# Doorlock-ESP32-copy_2026-03-03.net
KiCad netlist of a schematic drawn in Altium Designer
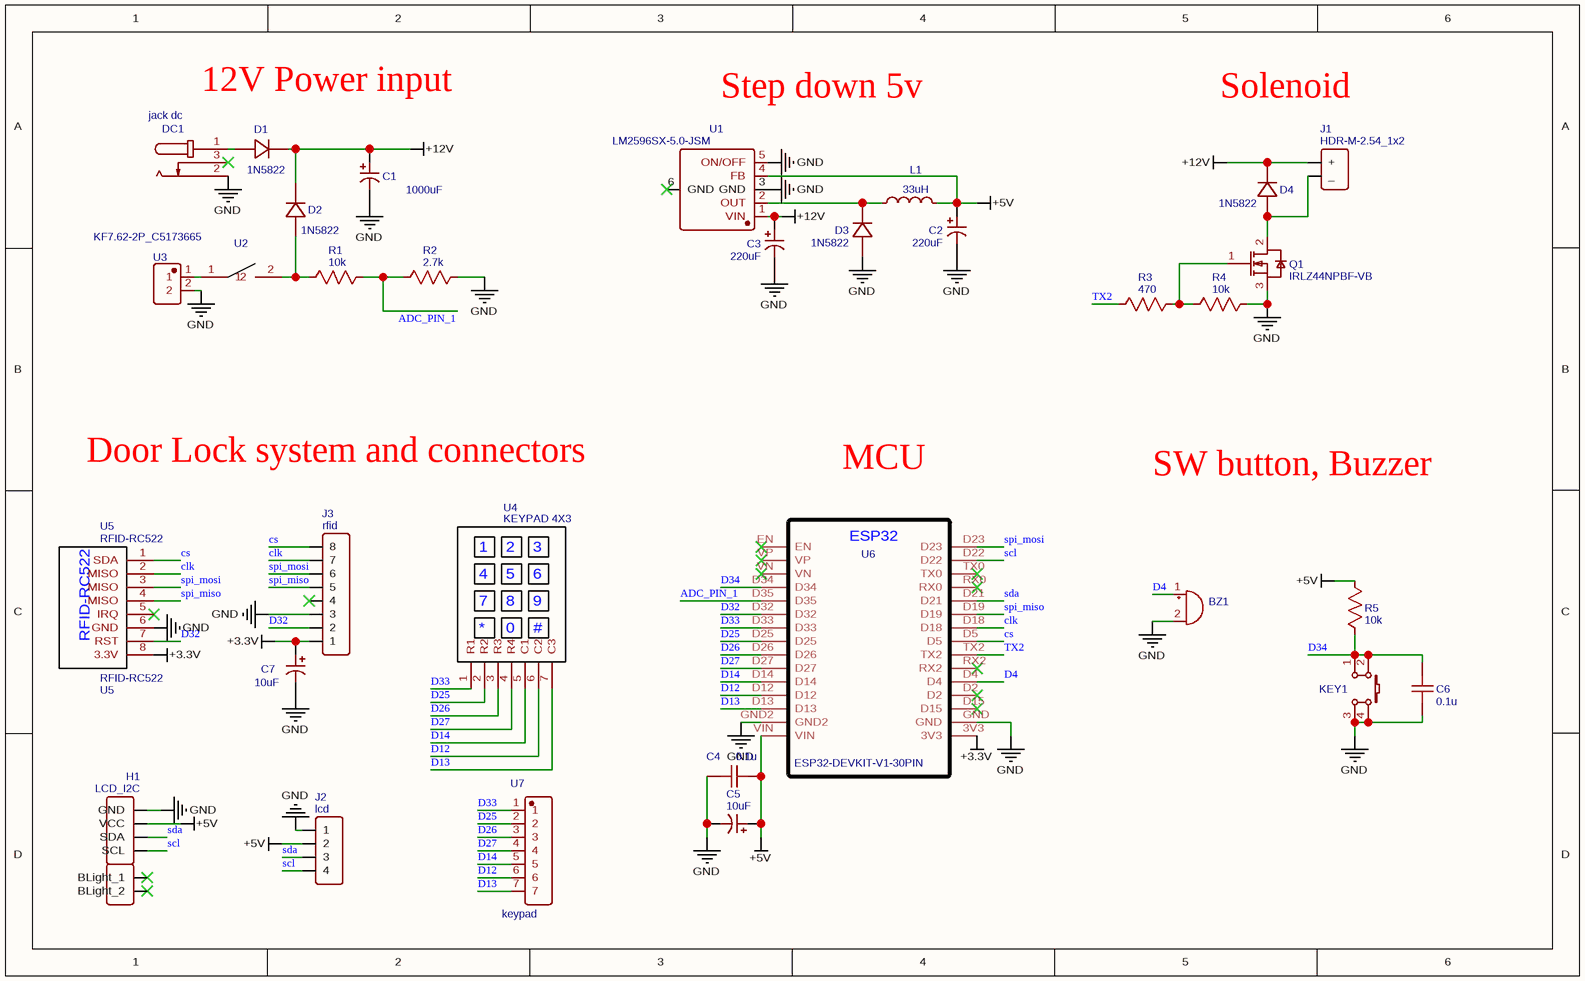
[diagram p0: Doorlock-ESP32-copy_2026-03-03.schdoc]

(export (version "E")
  (design (tool "Eeschema 10.0.6"))
  (components
    (comp (ref "BZ1")
      (value "DEVICE_BUZZER")
      (fields (field (name "CONTRIBUTOR") "anhnguyen0904255"))
      (libsource (lib "altium-import") (part "root_0_DEVICE_BUZZER_"))
    )
    (comp (ref "C1")
      (value "1000uF")
      (fields
        (field (name "MANUFACTURER") "HRK(鸿瑞凯电子)")
        (field (name "MANUFACTURER PART") "25V1000uF CD110")
        (field (name "CONTRIBUTOR") "lcsc")
      )
      (libsource (lib "altium-import") (part "root_3_1000uF_"))
    )
    (comp (ref "C2")
      (value "220uF")
      (fields
        (field (name "MANUFACTURER") "HRK(鸿瑞凯电子)")
        (field (name "MANUFACTURER PART") "25V1000uF CD110")
        (field (name "CONTRIBUTOR") "lcsc")
      )
      (libsource (lib "altium-import") (part "root_3_220uF_"))
    )
    (comp (ref "C3")
      (value "220uF")
      (fields
        (field (name "MANUFACTURER") "HRK(鸿瑞凯电子)")
        (field (name "MANUFACTURER PART") "25V1000uF CD110")
        (field (name "CONTRIBUTOR") "lcsc")
      )
      (libsource (lib "altium-import") (part "root_3_220uF_"))
    )
    (comp (ref "C4")
      (value "0.1u")
      (fields (field (name "CONTRIBUTOR") "LCEDA_Lib"))
      (libsource (lib "altium-import") (part "root_2_0.1u_"))
    )
    (comp (ref "C5")
      (value "10uF")
      (fields
        (field (name "MANUFACTURER") "Econd(米朗电子)")
        (field (name "MANUFACTURER PART") "10UF50VC110GL")
        (field (name "CONTRIBUTOR") "lcsc")
      )
      (libsource (lib "altium-import") (part "root_2_10uF_"))
    )
    (comp (ref "C6")
      (value "0.1u")
      (fields (field (name "CONTRIBUTOR") "LCEDA_Lib"))
      (libsource (lib "altium-import") (part "root_1_0.1u_"))
    )
    (comp (ref "C7")
      (value "10uF")
      (fields
        (field (name "MANUFACTURER") "Econd(米朗电子)")
        (field (name "MANUFACTURER PART") "10UF50VC110GL")
        (field (name "CONTRIBUTOR") "lcsc")
      )
      (libsource (lib "altium-import") (part "root_3_10uF_"))
    )
    (comp (ref "D1")
      (value "1N5822")
      (fields
        (field (name "MANUFACTURER") "YFW(佑风微)")
        (field (name "MANUFACTURER PART") "1N5819散装0658")
        (field (name "CONTRIBUTOR") "lcsc")
      )
      (libsource (lib "altium-import") (part "root_2_1N5822_"))
    )
    (comp (ref "D2")
      (value "1N5822")
      (fields
        (field (name "MANUFACTURER") "YFW(佑风微)")
        (field (name "MANUFACTURER PART") "1N5819散装0658")
        (field (name "CONTRIBUTOR") "lcsc")
      )
      (libsource (lib "altium-import") (part "root_3_1N5822_"))
    )
    (comp (ref "D3")
      (value "1N5822")
      (fields
        (field (name "MANUFACTURER") "YFW(佑风微)")
        (field (name "MANUFACTURER PART") "1N5819散装0658")
        (field (name "CONTRIBUTOR") "lcsc")
      )
      (libsource (lib "") (part "root_3_1N5822__1"))
    )
    (comp (ref "D4")
      (value "1N5822")
      (fields
        (field (name "MANUFACTURER") "YFW(佑风微)")
        (field (name "MANUFACTURER PART") "1N5819散装0658")
        (field (name "CONTRIBUTOR") "lcsc")
      )
      (libsource (lib "altium-import") (part "root_3_1N5822_"))
    )
    (comp (ref "DC1")
      (value "jack dc")
      (fields (field (name "MANUFACTURER") "SOFNG") (field (name "MANUFACTURER PART") "DC005-2.0MM"))
      (libsource (lib "altium-import") (part "root_0_jack dc_"))
    )
    (comp (ref "H1")
      (value "LCD_I2C")
      (fields (field (name "SUBPART_NO") "1") (field (name "CONTRIBUTOR") "amadosumbi3"))
      (libsource (lib "altium-import") (part "root_0_LCD_I2C_"))
    )
    (comp (ref "J1")
      (value "HDR-M-2.54_1x2")
      (fields (field (name "CONTRIBUTOR") "LCEDA_Lib"))
      (libsource (lib "altium-import") (part "root_0_HDR-M-2.54_1x2_"))
    )
    (comp (ref "J2")
      (value "lcd")
      (fields (field (name "CONTRIBUTOR") "LCEDA_Lib"))
      (libsource (lib "altium-import") (part "root_0_lcd_"))
    )
    (comp (ref "J3")
      (value "rfid")
      (fields (field (name "CONTRIBUTOR") "LCEDA_Lib"))
      (libsource (lib "altium-import") (part "root_2_rfid_"))
    )
    (comp (ref "KEY1")
      (value "K4-12×12_TH")
      (fields
        (field (name "MANUFACTURER") "韩国韩荣")
        (field (name "MANUFACTURER PART") "K2-1103DP-M4SW-04")
        (field (name "CONTRIBUTOR") "LCEDA_Lib")
      )
      (libsource (lib "altium-import") (part "root_3_K4-12×12_TH_"))
    )
    (comp (ref "L1")
      (value "33uH")
      (fields (field (name "CONTRIBUTOR") "LCEDA_Lib"))
      (libsource (lib "altium-import") (part "root_0_33uH_"))
    )
    (comp (ref "Q1")
      (value "IRLZ44NPBF-VB")
      (fields (field (name "MANUFACTURER") "VBsemi(微碧半导体)") (field (name "CONTRIBUTOR") "lcsc"))
      (libsource (lib "altium-import") (part "root_0_IRLZ44NPBF-VB_"))
    )
    (comp (ref "R1")
      (value "10k")
      (fields (field (name "CONTRIBUTOR") "LCEDA_Lib"))
      (libsource (lib "altium-import") (part "root_0_10k_"))
    )
    (comp (ref "R2")
      (value "2.7k")
      (fields (field (name "CONTRIBUTOR") "LCEDA_Lib"))
      (libsource (lib "altium-import") (part "root_0_2.7k_"))
    )
    (comp (ref "R3")
      (value "470")
      (fields (field (name "CONTRIBUTOR") "LCEDA_Lib"))
      (libsource (lib "altium-import") (part "root_0_470_"))
    )
    (comp (ref "R4")
      (value "10k")
      (fields (field (name "CONTRIBUTOR") "LCEDA_Lib"))
      (libsource (lib "altium-import") (part "root_0_10k_"))
    )
    (comp (ref "R5")
      (value "10k")
      (fields (field (name "CONTRIBUTOR") "LCEDA_Lib"))
      (libsource (lib "altium-import") (part "root_3_10k_"))
    )
    (comp (ref "U1")
      (value "LM2596SX-5.0-JSM")
      (fields (field (name "MANUFACTURER") "JSMSEMI(杰盛微)") (field (name "CONTRIBUTOR") "lcsc"))
      (libsource (lib "altium-import") (part "root_2_LM2596SX-5.0-JSM_"))
    )
    (comp (ref "U2")
      (value "HX KCD1-2P-P")
      (fields (field (name "MANUFACTURER") "hanxia(韩下)") (field (name "CONTRIBUTOR") "lcsc"))
      (libsource (lib "altium-import") (part "root_0_HX KCD1-2P-P_"))
    )
    (comp (ref "U3")
      (value "KF7.62-2P_C5173665")
      (fields
        (field (name "MANUFACTURER") "KEFA(科发)")
        (field (name "MANUFACTURER PART") "KF7.62-2P(green)")
        (field (name "CONTRIBUTOR") "lcsc")
      )
      (libsource (lib "altium-import") (part "root_0_KF7.62-2P_C5173665_"))
    )
    (comp (ref "U4")
      (value "KEYPAD 4X3")
      (fields (field (name "CONTRIBUTOR") "lucas.vissers"))
      (libsource (lib "altium-import") (part "root_0_KEYPAD 4X3_"))
    )
    (comp (ref "U5")
      (value "RFID-RC522")
      (fields (field (name "CONTRIBUTOR") "mayurharge"))
      (libsource (lib "altium-import") (part "root_0_RFID-RC522_"))
    )
    (comp (ref "U6")
      (value "ESP32-DEVKIT-V1-30PIN")
      (fields (field (name "CONTRIBUTOR") "juergs"))
      (libsource (lib "altium-import") (part "root_0_ESP32-DEVKIT-V1-30PIN_"))
    )
    (comp (ref "U7")
      (value "keypad")
      (fields (field (name "MANUFACTURER PART") "PZ2.54-1X7P-ZW") (field (name "CONTRIBUTOR") "LCSC"))
      (libsource (lib "altium-import") (part "root_2_keypad_"))
    )
  )
  (nets
    (net (code "1") (name "+3.3V") (class "Default")
      (node (ref "C7") (pin "1") (pinfunction "1_1") (pintype "passive"))
      (node (ref "J3") (pin "1") (pinfunction "1_1") (pintype "passive"))
      (node (ref "U5") (pin "8") (pinfunction "3.3V_8") (pintype "passive"))
      (node (ref "U6") (pin "3V3") (pinfunction "3V3_3V3") (pintype "passive"))
    )
    (net (code "2") (name "+5V") (class "Default")
      (node (ref "C2") (pin "1") (pinfunction "1_1") (pintype "passive"))
      (node (ref "C4") (pin "1") (pinfunction "1_1") (pintype "passive"))
      (node (ref "C5") (pin "1") (pinfunction "1_1") (pintype "passive"))
      (node (ref "H1") (pin "2") (pinfunction "VCC_2") (pintype "passive"))
      (node (ref "J2") (pin "2") (pinfunction "2_2") (pintype "passive"))
      (node (ref "L1") (pin "2") (pinfunction "2_2") (pintype "passive"))
      (node (ref "R5") (pin "1") (pinfunction "1_1") (pintype "passive"))
      (node (ref "U1") (pin "4") (pinfunction "FB_4") (pintype "passive"))
      (node (ref "U6") (pin "VIN") (pinfunction "VIN_VIN") (pintype "passive"))
    )
    (net (code "3") (name "+12V") (class "Default")
      (node (ref "C1") (pin "1") (pinfunction "1_1") (pintype "passive"))
      (node (ref "C3") (pin "1") (pinfunction "1_1") (pintype "passive"))
      (node (ref "D1") (pin "1") (pinfunction "K_1") (pintype "passive"))
      (node (ref "D2") (pin "1") (pinfunction "K_1") (pintype "passive"))
      (node (ref "D4") (pin "1") (pinfunction "K_1") (pintype "passive"))
      (node (ref "J1") (pin "1") (pinfunction "+_1") (pintype "passive"))
      (node (ref "U1") (pin "1") (pinfunction "VIN_1") (pintype "passive"))
    )
    (net (code "4") (name "/ADC_PIN_1") (class "Default")
      (node (ref "R1") (pin "2") (pinfunction "2_2") (pintype "passive"))
      (node (ref "R2") (pin "1") (pinfunction "1_1") (pintype "passive"))
      (node (ref "U6") (pin "D35") (pinfunction "D35_D35") (pintype "passive"))
    )
    (net (code "5") (name "/D4") (class "Default")
      (node (ref "BZ1") (pin "1") (pinfunction "+_1") (pintype "passive"))
      (node (ref "U6") (pin "D4") (pinfunction "D4_D4") (pintype "passive"))
    )
    (net (code "6") (name "/D12") (class "Default")
      (node (ref "U4") (pin "6") (pinfunction "C2_6") (pintype "passive"))
      (node (ref "U6") (pin "D12") (pinfunction "D12_D12") (pintype "passive"))
      (node (ref "U7") (pin "6") (pinfunction "6_6") (pintype "passive"))
    )
    (net (code "7") (name "/D13") (class "Default")
      (node (ref "U4") (pin "7") (pinfunction "C3_7") (pintype "passive"))
      (node (ref "U6") (pin "D13") (pinfunction "D13_D13") (pintype "passive"))
      (node (ref "U7") (pin "7") (pinfunction "7_7") (pintype "passive"))
    )
    (net (code "8") (name "/D14") (class "Default")
      (node (ref "U4") (pin "5") (pinfunction "C1_5") (pintype "passive"))
      (node (ref "U6") (pin "D14") (pinfunction "D14_D14") (pintype "passive"))
      (node (ref "U7") (pin "5") (pinfunction "5_5") (pintype "passive"))
    )
    (net (code "9") (name "/D25") (class "Default")
      (node (ref "U4") (pin "2") (pinfunction "R2_2") (pintype "passive"))
      (node (ref "U6") (pin "D25") (pinfunction "D25_D25") (pintype "passive"))
      (node (ref "U7") (pin "2") (pinfunction "2_2") (pintype "passive"))
    )
    (net (code "10") (name "/D26") (class "Default")
      (node (ref "U4") (pin "3") (pinfunction "R3_3") (pintype "passive"))
      (node (ref "U6") (pin "D26") (pinfunction "D26_D26") (pintype "passive"))
      (node (ref "U7") (pin "3") (pinfunction "3_3") (pintype "passive"))
    )
    (net (code "11") (name "/D27") (class "Default")
      (node (ref "U4") (pin "4") (pinfunction "R4_4") (pintype "passive"))
      (node (ref "U6") (pin "D27") (pinfunction "D27_D27") (pintype "passive"))
      (node (ref "U7") (pin "4") (pinfunction "4_4") (pintype "passive"))
    )
    (net (code "12") (name "/D32") (class "Default")
      (node (ref "J3") (pin "2") (pinfunction "2_2") (pintype "passive"))
      (node (ref "U5") (pin "7") (pinfunction "RST_7") (pintype "passive"))
      (node (ref "U6") (pin "D32") (pinfunction "D32_D32") (pintype "passive"))
    )
    (net (code "13") (name "/D33") (class "Default")
      (node (ref "U4") (pin "1") (pinfunction "R1_1") (pintype "passive"))
      (node (ref "U6") (pin "D33") (pinfunction "D33_D33") (pintype "passive"))
      (node (ref "U7") (pin "1") (pinfunction "1_1") (pintype "passive"))
    )
    (net (code "14") (name "/D34") (class "Default")
      (node (ref "C6") (pin "2") (pinfunction "2_2") (pintype "passive"))
      (node (ref "KEY1") (pin "1") (pinfunction "1_1") (pintype "passive"))
      (node (ref "KEY1") (pin "2") (pinfunction "2_2") (pintype "passive"))
      (node (ref "R5") (pin "2") (pinfunction "2_2") (pintype "passive"))
      (node (ref "U6") (pin "D34") (pinfunction "D34_D34") (pintype "passive"))
    )
    (net (code "15") (name "/TX2") (class "Default")
      (node (ref "R3") (pin "1") (pinfunction "1_1") (pintype "passive"))
      (node (ref "U6") (pin "TX2") (pinfunction "TX2_TX2") (pintype "passive"))
    )
    (net (code "16") (name "/clk") (class "Default")
      (node (ref "J3") (pin "7") (pinfunction "7_7") (pintype "passive"))
      (node (ref "U5") (pin "2") (pinfunction "MISO_2") (pintype "passive"))
      (node (ref "U6") (pin "D18") (pinfunction "D18_D18") (pintype "passive"))
    )
    (net (code "17") (name "/cs") (class "Default")
      (node (ref "J3") (pin "8") (pinfunction "8_8") (pintype "passive"))
      (node (ref "U5") (pin "1") (pinfunction "SDA_1") (pintype "passive"))
      (node (ref "U6") (pin "D5") (pinfunction "D5_D5") (pintype "passive"))
    )
    (net (code "18") (name "/scl") (class "Default")
      (node (ref "H1") (pin "4") (pinfunction "SCL_4") (pintype "passive"))
      (node (ref "J2") (pin "4") (pinfunction "4_4") (pintype "passive"))
      (node (ref "U6") (pin "D22") (pinfunction "D22_D22") (pintype "passive"))
    )
    (net (code "19") (name "/sda") (class "Default")
      (node (ref "H1") (pin "3") (pinfunction "SDA_3") (pintype "passive"))
      (node (ref "J2") (pin "3") (pinfunction "3_3") (pintype "passive"))
      (node (ref "U6") (pin "D21") (pinfunction "D21_D21") (pintype "passive"))
    )
    (net (code "20") (name "/spi_miso") (class "Default")
      (node (ref "J3") (pin "5") (pinfunction "5_5") (pintype "passive"))
      (node (ref "U5") (pin "4") (pinfunction "MISO_4") (pintype "passive"))
      (node (ref "U6") (pin "D19") (pinfunction "D19_D19") (pintype "passive"))
    )
    (net (code "21") (name "/spi_mosi") (class "Default")
      (node (ref "J3") (pin "6") (pinfunction "6_6") (pintype "passive"))
      (node (ref "U5") (pin "3") (pinfunction "MISO_3") (pintype "passive"))
      (node (ref "U6") (pin "D23") (pinfunction "D23_D23") (pintype "passive"))
    )
    (net (code "22") (name "GND") (class "Default")
      (node (ref "BZ1") (pin "2") (pinfunction "-_2") (pintype "passive"))
      (node (ref "C1") (pin "2") (pinfunction "2_2") (pintype "passive"))
      (node (ref "C2") (pin "2") (pinfunction "2_2") (pintype "passive"))
      (node (ref "C3") (pin "2") (pinfunction "2_2") (pintype "passive"))
      (node (ref "C4") (pin "2") (pinfunction "2_2") (pintype "passive"))
      (node (ref "C5") (pin "2") (pinfunction "2_2") (pintype "passive"))
      (node (ref "C6") (pin "1") (pinfunction "1_1") (pintype "passive"))
      (node (ref "C7") (pin "2") (pinfunction "2_2") (pintype "passive"))
      (node (ref "D3") (pin "2") (pinfunction "A_2") (pintype "passive"))
      (node (ref "DC1") (pin "2") (pinfunction "2_2") (pintype "passive"))
      (node (ref "H1") (pin "1") (pinfunction "GND_1") (pintype "passive"))
      (node (ref "J2") (pin "1") (pinfunction "1_1") (pintype "passive"))
      (node (ref "J3") (pin "3") (pinfunction "3_3") (pintype "passive"))
      (node (ref "KEY1") (pin "3") (pinfunction "3_3") (pintype "passive"))
      (node (ref "KEY1") (pin "4") (pinfunction "4_4") (pintype "passive"))
      (node (ref "Q1") (pin "3") (pinfunction "S_3") (pintype "passive"))
      (node (ref "R2") (pin "2") (pinfunction "2_2") (pintype "passive"))
      (node (ref "R4") (pin "2") (pinfunction "2_2") (pintype "passive"))
      (node (ref "U1") (pin "3") (pinfunction "GND_3") (pintype "passive"))
      (node (ref "U1") (pin "5") (pinfunction "ON/OFF_5") (pintype "passive"))
      (node (ref "U3") (pin "2") (pinfunction "2_2") (pintype "passive"))
      (node (ref "U5") (pin "6") (pinfunction "GND_6") (pintype "passive"))
      (node (ref "U6") (pin "GND") (pinfunction "GND_GND") (pintype "passive"))
      (node (ref "U6") (pin "GND2") (pinfunction "GND2_GND2") (pintype "passive"))
    )
    (net (code "23") (name "Net-(D1-A)") (class "Default")
      (node (ref "D1") (pin "2") (pinfunction "A_2") (pintype "passive"))
      (node (ref "DC1") (pin "1") (pinfunction "1_1") (pintype "passive"))
    )
    (net (code "24") (name "Net-(D2-A)") (class "Default")
      (node (ref "D2") (pin "2") (pinfunction "A_2") (pintype "passive"))
      (node (ref "R1") (pin "1") (pinfunction "1_1") (pintype "passive"))
      (node (ref "U2") (pin "2") (pinfunction "2_2") (pintype "passive"))
    )
    (net (code "25") (name "Net-(D3-K)") (class "Default")
      (node (ref "D3") (pin "1") (pinfunction "K_1") (pintype "passive"))
      (node (ref "L1") (pin "1") (pinfunction "1_1") (pintype "passive"))
      (node (ref "U1") (pin "2") (pinfunction "OUT_2") (pintype "passive"))
    )
    (net (code "26") (name "Net-(D4-A)") (class "Default")
      (node (ref "D4") (pin "2") (pinfunction "A_2") (pintype "passive"))
      (node (ref "J1") (pin "2") (pinfunction "__2") (pintype "passive"))
      (node (ref "Q1") (pin "2") (pinfunction "D_2") (pintype "passive"))
    )
    (net (code "27") (name "Net-(Q1-G)") (class "Default")
      (node (ref "Q1") (pin "1") (pinfunction "G_1") (pintype "passive"))
      (node (ref "R3") (pin "2") (pinfunction "2_2") (pintype "passive"))
      (node (ref "R4") (pin "1") (pinfunction "1_1") (pintype "passive"))
    )
    (net (code "28") (name "Net-(U2-Pad1)") (class "Default")
      (node (ref "U2") (pin "1") (pinfunction "1_1") (pintype "passive"))
      (node (ref "U3") (pin "1") (pinfunction "1_1") (pintype "passive"))
    )
    (net (code "29") (name "unconnected-(DC1-Pad3)") (class "Default")
      (node (ref "DC1") (pin "3") (pinfunction "3_3") (pintype "passive+no_connect"))
    )
    (net (code "30") (name "unconnected-(H1-BLight_1-Pad5)") (class "Default")
      (node (ref "H1") (pin "5") (pinfunction "BLight_1_5") (pintype "passive+no_connect"))
    )
    (net (code "31") (name "unconnected-(H1-BLight_2-Pad6)") (class "Default")
      (node (ref "H1") (pin "6") (pinfunction "BLight_2_6") (pintype "passive+no_connect"))
    )
    (net (code "32") (name "unconnected-(J3-Pad4)") (class "Default")
      (node (ref "J3") (pin "4") (pinfunction "4_4") (pintype "passive+no_connect"))
    )
    (net (code "33") (name "unconnected-(U1-GND-Pad6)") (class "Default")
      (node (ref "U1") (pin "6") (pinfunction "GND_6") (pintype "passive+no_connect"))
    )
    (net (code "34") (name "unconnected-(U5-IRQ-Pad5)") (class "Default")
      (node (ref "U5") (pin "5") (pinfunction "IRQ_5") (pintype "passive+no_connect"))
    )
    (net (code "35") (name "unconnected-(U6-PadD2)") (class "Default")
      (node (ref "U6") (pin "D2") (pinfunction "D2_D2") (pintype "passive+no_connect"))
    )
    (net (code "36") (name "unconnected-(U6-PadD15)") (class "Default")
      (node (ref "U6") (pin "D15") (pinfunction "D15_D15") (pintype "passive+no_connect"))
    )
    (net (code "37") (name "unconnected-(U6-PadEN)") (class "Default")
      (node (ref "U6") (pin "EN") (pinfunction "EN_EN") (pintype "passive+no_connect"))
    )
    (net (code "38") (name "unconnected-(U6-PadRX0)") (class "Default")
      (node (ref "U6") (pin "RX0") (pinfunction "RX0_RX0") (pintype "passive+no_connect"))
    )
    (net (code "39") (name "unconnected-(U6-PadRX2)") (class "Default")
      (node (ref "U6") (pin "RX2") (pinfunction "RX2_RX2") (pintype "passive+no_connect"))
    )
    (net (code "40") (name "unconnected-(U6-PadTX0)") (class "Default")
      (node (ref "U6") (pin "TX0") (pinfunction "TX0_TX0") (pintype "passive+no_connect"))
    )
    (net (code "41") (name "unconnected-(U6-PadVN)") (class "Default")
      (node (ref "U6") (pin "VN") (pinfunction "VN_VN") (pintype "passive+no_connect"))
    )
    (net (code "42") (name "unconnected-(U6-PadVP)") (class "Default")
      (node (ref "U6") (pin "VP") (pinfunction "VP_VP") (pintype "passive+no_connect"))
    )
  )
)
